# SDcard_final_rev02.net
KiCad netlist of a schematic drawn in EAGLE
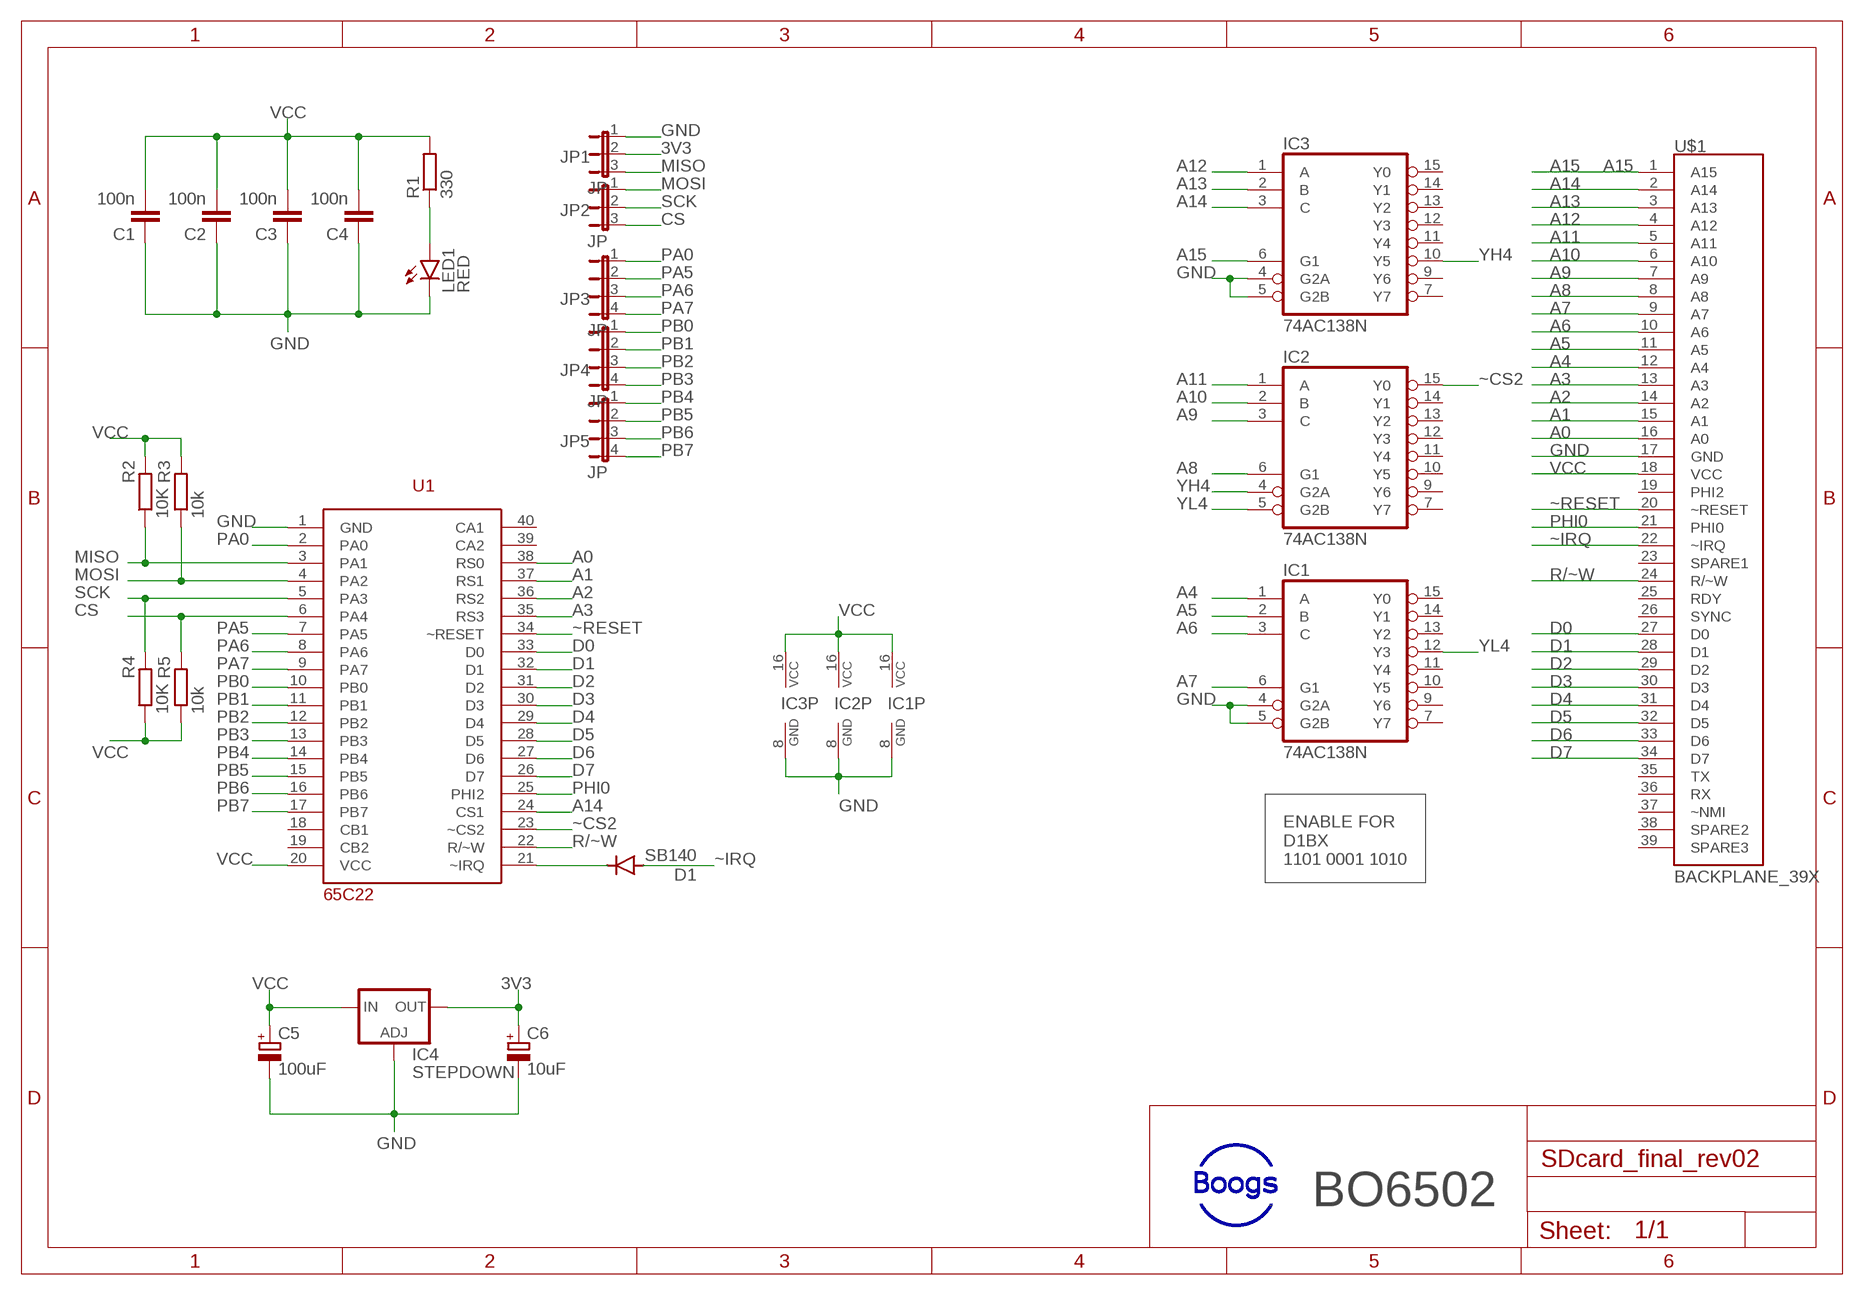
[diagram p0: schematic, sheet 1]

(export (version "E")
  (design (tool "Eeschema 10.0.6"))
  (components
    (comp (ref "C1")
      (value "100n")
      (footprint "eagle-import:C025-025X050")
      (libsource (lib "eagle-import") (part "C-EU025-025X050"))
    )
    (comp (ref "C2")
      (value "100n")
      (footprint "eagle-import:C025-025X050")
      (libsource (lib "eagle-import") (part "C-EU025-025X050"))
    )
    (comp (ref "C3")
      (value "100n")
      (footprint "eagle-import:C025-025X050")
      (libsource (lib "eagle-import") (part "C-EU025-025X050"))
    )
    (comp (ref "C4")
      (value "100n")
      (footprint "eagle-import:C025-025X050")
      (libsource (lib "eagle-import") (part "C-EU025-025X050"))
    )
    (comp (ref "C5")
      (value "100uF")
      (footprint "eagle-import:B45181A")
      (libsource (lib "eagle-import") (part "CPOL-EUB45181A"))
    )
    (comp (ref "C6")
      (value "10uF")
      (footprint "eagle-import:B45181A")
      (libsource (lib "eagle-import") (part "CPOL-EUB45181A"))
    )
    (comp (ref "D1")
      (value "SB140")
      (footprint "eagle-import:DO41-10")
      (libsource (lib "eagle-import") (part "1N4004"))
    )
    (comp (ref "IC1")
      (value "74AC138N")
      (footprint "eagle-import:DIL16")
      (libsource (lib "eagle-import") (part "74138NAC"))
    )
    (comp (ref "IC2")
      (value "74AC138N")
      (footprint "eagle-import:DIL16")
      (libsource (lib "eagle-import") (part "74138NAC"))
    )
    (comp (ref "IC3")
      (value "74AC138N")
      (footprint "eagle-import:DIL16")
      (libsource (lib "eagle-import") (part "74138NAC"))
    )
    (comp (ref "IC4")
      (value "STEPDOWN")
      (footprint "eagle-import:317TS")
      (libsource (lib "eagle-import") (part "LM317TS"))
    )
    (comp (ref "JP1")
      (value "JP")
      (footprint "eagle-import:JP2")
      (libsource (lib "eagle-import") (part "JP2E"))
    )
    (comp (ref "JP2")
      (value "JP")
      (footprint "eagle-import:JP2")
      (libsource (lib "eagle-import") (part "JP2E"))
    )
    (comp (ref "JP3")
      (value "JP")
      (footprint "eagle-import:JP4")
      (libsource (lib "eagle-import") (part "JP4E"))
    )
    (comp (ref "JP4")
      (value "JP")
      (footprint "eagle-import:JP4")
      (libsource (lib "eagle-import") (part "JP4E"))
    )
    (comp (ref "JP5")
      (value "JP")
      (footprint "eagle-import:JP4")
      (libsource (lib "eagle-import") (part "JP4E"))
    )
    (comp (ref "LED1")
      (value "RED")
      (footprint "eagle-import:LED5MM")
      (libsource (lib "eagle-import") (part "LED5MM"))
    )
    (comp (ref "R1")
      (value "330")
      (footprint "eagle-import:0207_10")
      (libsource (lib "eagle-import") (part "R-EU_0207/10"))
    )
    (comp (ref "R2")
      (value "10K")
      (footprint "eagle-import:0207_10")
      (libsource (lib "eagle-import") (part "R-EU_0207/10"))
    )
    (comp (ref "R3")
      (value "10k")
      (footprint "eagle-import:0207_10")
      (libsource (lib "eagle-import") (part "R-EU_0207/10"))
    )
    (comp (ref "R4")
      (value "10K")
      (footprint "eagle-import:0207_10")
      (libsource (lib "eagle-import") (part "R-EU_0207/10"))
    )
    (comp (ref "R5")
      (value "10k")
      (footprint "eagle-import:0207_10")
      (libsource (lib "eagle-import") (part "R-EU_0207/10"))
    )
    (comp (ref "U$1")
      (value "BACKPLANE_39X")
      (footprint "eagle-import:BP_39X")
      (fields (field (name "A15") "A15"))
      (libsource (lib "eagle-import") (part "BACKPLANE_39X"))
    )
    (comp (ref "U1")
      (value "65C22")
      (footprint "eagle-import:DIL40")
      (libsource (lib "eagle-import") (part "65C22"))
    )
  )
  (nets
    (net (code "1") (name "/3V3") (class "Default")
      (node (ref "C6") (pin "+") (pinfunction "+_+") (pintype "passive"))
      (node (ref "IC4") (pin "2") (pinfunction "OUT_2") (pintype "passive"))
      (node (ref "JP1") (pin "2") (pinfunction "2_2") (pintype "passive"))
    )
    (net (code "2") (name "/A0") (class "Default")
      (node (ref "U$1") (pin "16") (pinfunction "A0_16") (pintype "bidirectional"))
      (node (ref "U1") (pin "38") (pinfunction "RS0_38") (pintype "bidirectional"))
    )
    (net (code "3") (name "/A1") (class "Default")
      (node (ref "U$1") (pin "15") (pinfunction "A1_15") (pintype "bidirectional"))
      (node (ref "U1") (pin "37") (pinfunction "RS1_37") (pintype "bidirectional"))
    )
    (net (code "4") (name "/A2") (class "Default")
      (node (ref "U$1") (pin "14") (pinfunction "A2_14") (pintype "bidirectional"))
      (node (ref "U1") (pin "36") (pinfunction "RS2_36") (pintype "bidirectional"))
    )
    (net (code "5") (name "/A3") (class "Default")
      (node (ref "U$1") (pin "13") (pinfunction "A3_13") (pintype "bidirectional"))
      (node (ref "U1") (pin "35") (pinfunction "RS3_35") (pintype "bidirectional"))
    )
    (net (code "6") (name "/A4") (class "Default")
      (node (ref "IC1") (pin "1") (pinfunction "A_1") (pintype "input"))
      (node (ref "U$1") (pin "12") (pinfunction "A4_12") (pintype "bidirectional"))
    )
    (net (code "7") (name "/A5") (class "Default")
      (node (ref "IC1") (pin "2") (pinfunction "B_2") (pintype "input"))
      (node (ref "U$1") (pin "11") (pinfunction "A5_11") (pintype "bidirectional"))
    )
    (net (code "8") (name "/A6") (class "Default")
      (node (ref "IC1") (pin "3") (pinfunction "C_3") (pintype "input"))
      (node (ref "U$1") (pin "10") (pinfunction "A6_10") (pintype "bidirectional"))
    )
    (net (code "9") (name "/A7") (class "Default")
      (node (ref "IC1") (pin "6") (pinfunction "G1_6") (pintype "input"))
      (node (ref "U$1") (pin "9") (pinfunction "A7_9") (pintype "bidirectional"))
    )
    (net (code "10") (name "/A8") (class "Default")
      (node (ref "IC2") (pin "6") (pinfunction "G1_6") (pintype "input"))
      (node (ref "U$1") (pin "8") (pinfunction "A8_8") (pintype "bidirectional"))
    )
    (net (code "11") (name "/A9") (class "Default")
      (node (ref "IC2") (pin "3") (pinfunction "C_3") (pintype "input"))
      (node (ref "U$1") (pin "7") (pinfunction "A9_7") (pintype "bidirectional"))
    )
    (net (code "12") (name "/A10") (class "Default")
      (node (ref "IC2") (pin "2") (pinfunction "B_2") (pintype "input"))
      (node (ref "U$1") (pin "6") (pinfunction "A10_6") (pintype "bidirectional"))
    )
    (net (code "13") (name "/A11") (class "Default")
      (node (ref "IC2") (pin "1") (pinfunction "A_1") (pintype "input"))
      (node (ref "U$1") (pin "5") (pinfunction "A11_5") (pintype "bidirectional"))
    )
    (net (code "14") (name "/A12") (class "Default")
      (node (ref "IC3") (pin "1") (pinfunction "A_1") (pintype "input"))
      (node (ref "U$1") (pin "4") (pinfunction "A12_4") (pintype "bidirectional"))
    )
    (net (code "15") (name "/A13") (class "Default")
      (node (ref "IC3") (pin "2") (pinfunction "B_2") (pintype "input"))
      (node (ref "U$1") (pin "3") (pinfunction "A13_3") (pintype "bidirectional"))
    )
    (net (code "16") (name "/A14") (class "Default")
      (node (ref "IC3") (pin "3") (pinfunction "C_3") (pintype "input"))
      (node (ref "U$1") (pin "2") (pinfunction "A14_2") (pintype "bidirectional"))
      (node (ref "U1") (pin "24") (pinfunction "CS1_24") (pintype "bidirectional"))
    )
    (net (code "17") (name "/A15") (class "Default")
      (node (ref "IC3") (pin "6") (pinfunction "G1_6") (pintype "input"))
      (node (ref "U$1") (pin "1") (pinfunction "A15_1") (pintype "bidirectional"))
    )
    (net (code "18") (name "/CS") (class "Default")
      (node (ref "JP2") (pin "3") (pinfunction "3_3") (pintype "passive"))
      (node (ref "R5") (pin "2") (pinfunction "2_2") (pintype "passive"))
      (node (ref "U1") (pin "6") (pinfunction "PA4_6") (pintype "bidirectional"))
    )
    (net (code "19") (name "/D0") (class "Default")
      (node (ref "U$1") (pin "27") (pinfunction "D0_27") (pintype "bidirectional"))
      (node (ref "U1") (pin "33") (pinfunction "D0_33") (pintype "bidirectional"))
    )
    (net (code "20") (name "/D1") (class "Default")
      (node (ref "U$1") (pin "28") (pinfunction "D1_28") (pintype "bidirectional"))
      (node (ref "U1") (pin "32") (pinfunction "D1_32") (pintype "bidirectional"))
    )
    (net (code "21") (name "/D2") (class "Default")
      (node (ref "U$1") (pin "29") (pinfunction "D2_29") (pintype "bidirectional"))
      (node (ref "U1") (pin "31") (pinfunction "D2_31") (pintype "bidirectional"))
    )
    (net (code "22") (name "/D3") (class "Default")
      (node (ref "U$1") (pin "30") (pinfunction "D3_30") (pintype "bidirectional"))
      (node (ref "U1") (pin "30") (pinfunction "D3_30") (pintype "bidirectional"))
    )
    (net (code "23") (name "/D4") (class "Default")
      (node (ref "U$1") (pin "31") (pinfunction "D4_31") (pintype "bidirectional"))
      (node (ref "U1") (pin "29") (pinfunction "D4_29") (pintype "bidirectional"))
    )
    (net (code "24") (name "/D5") (class "Default")
      (node (ref "U$1") (pin "32") (pinfunction "D5_32") (pintype "bidirectional"))
      (node (ref "U1") (pin "28") (pinfunction "D5_28") (pintype "bidirectional"))
    )
    (net (code "25") (name "/D6") (class "Default")
      (node (ref "U$1") (pin "33") (pinfunction "D6_33") (pintype "bidirectional"))
      (node (ref "U1") (pin "27") (pinfunction "D6_27") (pintype "bidirectional"))
    )
    (net (code "26") (name "/D7") (class "Default")
      (node (ref "U$1") (pin "34") (pinfunction "D7_34") (pintype "bidirectional"))
      (node (ref "U1") (pin "26") (pinfunction "D7_26") (pintype "bidirectional"))
    )
    (net (code "27") (name "/GND") (class "Default")
      (node (ref "C1") (pin "1") (pinfunction "1_1") (pintype "passive"))
      (node (ref "C2") (pin "1") (pinfunction "1_1") (pintype "passive"))
      (node (ref "C3") (pin "1") (pinfunction "1_1") (pintype "passive"))
      (node (ref "C4") (pin "1") (pinfunction "1_1") (pintype "passive"))
      (node (ref "C5") (pin "-") (pinfunction "-_-") (pintype "passive"))
      (node (ref "C6") (pin "-") (pinfunction "-_-") (pintype "passive"))
      (node (ref "IC1") (pin "4") (pinfunction "G2A_4") (pintype "input"))
      (node (ref "IC1") (pin "5") (pinfunction "G2B_5") (pintype "input"))
      (node (ref "IC1") (pin "8") (pinfunction "GND_8") (pintype "power_in"))
      (node (ref "IC2") (pin "8") (pinfunction "GND_8") (pintype "power_in"))
      (node (ref "IC3") (pin "4") (pinfunction "G2A_4") (pintype "input"))
      (node (ref "IC3") (pin "5") (pinfunction "G2B_5") (pintype "input"))
      (node (ref "IC3") (pin "8") (pinfunction "GND_8") (pintype "power_in"))
      (node (ref "IC4") (pin "1") (pinfunction "ADJ_1") (pintype "input"))
      (node (ref "JP1") (pin "1") (pinfunction "1_1") (pintype "passive"))
      (node (ref "LED1") (pin "K") (pinfunction "C_K") (pintype "passive"))
      (node (ref "U$1") (pin "17") (pinfunction "GND_17") (pintype "bidirectional"))
      (node (ref "U1") (pin "1") (pinfunction "GND_1") (pintype "bidirectional"))
    )
    (net (code "28") (name "/MISO") (class "Default")
      (node (ref "JP1") (pin "3") (pinfunction "3_3") (pintype "passive"))
      (node (ref "R2") (pin "1") (pinfunction "1_1") (pintype "passive"))
      (node (ref "U1") (pin "3") (pinfunction "PA1_3") (pintype "bidirectional"))
    )
    (net (code "29") (name "/MOSI") (class "Default")
      (node (ref "JP2") (pin "1") (pinfunction "1_1") (pintype "passive"))
      (node (ref "R3") (pin "1") (pinfunction "1_1") (pintype "passive"))
      (node (ref "U1") (pin "4") (pinfunction "PA2_4") (pintype "bidirectional"))
    )
    (net (code "30") (name "/PA0") (class "Default")
      (node (ref "JP3") (pin "1") (pinfunction "1_1") (pintype "passive"))
      (node (ref "U1") (pin "2") (pinfunction "PA0_2") (pintype "bidirectional"))
    )
    (net (code "31") (name "/PA5") (class "Default")
      (node (ref "JP3") (pin "2") (pinfunction "2_2") (pintype "passive"))
      (node (ref "U1") (pin "7") (pinfunction "PA5_7") (pintype "bidirectional"))
    )
    (net (code "32") (name "/PA6") (class "Default")
      (node (ref "JP3") (pin "3") (pinfunction "3_3") (pintype "passive"))
      (node (ref "U1") (pin "8") (pinfunction "PA6_8") (pintype "bidirectional"))
    )
    (net (code "33") (name "/PA7") (class "Default")
      (node (ref "JP3") (pin "4") (pinfunction "4_4") (pintype "passive"))
      (node (ref "U1") (pin "9") (pinfunction "PA7_9") (pintype "bidirectional"))
    )
    (net (code "34") (name "/PB0") (class "Default")
      (node (ref "JP4") (pin "1") (pinfunction "1_1") (pintype "passive"))
      (node (ref "U1") (pin "10") (pinfunction "PB0_10") (pintype "bidirectional"))
    )
    (net (code "35") (name "/PB1") (class "Default")
      (node (ref "JP4") (pin "2") (pinfunction "2_2") (pintype "passive"))
      (node (ref "U1") (pin "11") (pinfunction "PB1_11") (pintype "bidirectional"))
    )
    (net (code "36") (name "/PB2") (class "Default")
      (node (ref "JP4") (pin "3") (pinfunction "3_3") (pintype "passive"))
      (node (ref "U1") (pin "12") (pinfunction "PB2_12") (pintype "bidirectional"))
    )
    (net (code "37") (name "/PB3") (class "Default")
      (node (ref "JP4") (pin "4") (pinfunction "4_4") (pintype "passive"))
      (node (ref "U1") (pin "13") (pinfunction "PB3_13") (pintype "bidirectional"))
    )
    (net (code "38") (name "/PB4") (class "Default")
      (node (ref "JP5") (pin "1") (pinfunction "1_1") (pintype "passive"))
      (node (ref "U1") (pin "14") (pinfunction "PB4_14") (pintype "bidirectional"))
    )
    (net (code "39") (name "/PB5") (class "Default")
      (node (ref "JP5") (pin "2") (pinfunction "2_2") (pintype "passive"))
      (node (ref "U1") (pin "15") (pinfunction "PB5_15") (pintype "bidirectional"))
    )
    (net (code "40") (name "/PB6") (class "Default")
      (node (ref "JP5") (pin "3") (pinfunction "3_3") (pintype "passive"))
      (node (ref "U1") (pin "16") (pinfunction "PB6_16") (pintype "bidirectional"))
    )
    (net (code "41") (name "/PB7") (class "Default")
      (node (ref "JP5") (pin "4") (pinfunction "4_4") (pintype "passive"))
      (node (ref "U1") (pin "17") (pinfunction "PB7_17") (pintype "bidirectional"))
    )
    (net (code "42") (name "/PHI0") (class "Default")
      (node (ref "U$1") (pin "21") (pinfunction "PHI0_21") (pintype "bidirectional"))
      (node (ref "U1") (pin "25") (pinfunction "PHI2_25") (pintype "bidirectional"))
    )
    (net (code "43") (name "/R{slash}~{W}") (class "Default")
      (node (ref "U$1") (pin "24") (pinfunction "R/~{W}_24") (pintype "bidirectional"))
      (node (ref "U1") (pin "22") (pinfunction "R/~{W}_22") (pintype "bidirectional"))
    )
    (net (code "44") (name "/SCK") (class "Default")
      (node (ref "JP2") (pin "2") (pinfunction "2_2") (pintype "passive"))
      (node (ref "R4") (pin "2") (pinfunction "2_2") (pintype "passive"))
      (node (ref "U1") (pin "5") (pinfunction "PA3_5") (pintype "bidirectional"))
    )
    (net (code "45") (name "/VCC") (class "Default")
      (node (ref "C1") (pin "2") (pinfunction "2_2") (pintype "passive"))
      (node (ref "C2") (pin "2") (pinfunction "2_2") (pintype "passive"))
      (node (ref "C3") (pin "2") (pinfunction "2_2") (pintype "passive"))
      (node (ref "C4") (pin "2") (pinfunction "2_2") (pintype "passive"))
      (node (ref "C5") (pin "+") (pinfunction "+_+") (pintype "passive"))
      (node (ref "IC1") (pin "16") (pinfunction "VCC_16") (pintype "power_in"))
      (node (ref "IC2") (pin "16") (pinfunction "VCC_16") (pintype "power_in"))
      (node (ref "IC3") (pin "16") (pinfunction "VCC_16") (pintype "power_in"))
      (node (ref "IC4") (pin "3") (pinfunction "IN_3") (pintype "input"))
      (node (ref "R1") (pin "2") (pinfunction "2_2") (pintype "passive"))
      (node (ref "R2") (pin "2") (pinfunction "2_2") (pintype "passive"))
      (node (ref "R3") (pin "2") (pinfunction "2_2") (pintype "passive"))
      (node (ref "R4") (pin "1") (pinfunction "1_1") (pintype "passive"))
      (node (ref "R5") (pin "1") (pinfunction "1_1") (pintype "passive"))
      (node (ref "U$1") (pin "18") (pinfunction "VCC_18") (pintype "bidirectional"))
      (node (ref "U1") (pin "20") (pinfunction "VCC_20") (pintype "bidirectional"))
    )
    (net (code "46") (name "/YH4") (class "Default")
      (node (ref "IC2") (pin "4") (pinfunction "G2A_4") (pintype "input"))
      (node (ref "IC3") (pin "10") (pinfunction "Y5_10") (pintype "output"))
    )
    (net (code "47") (name "/YL4") (class "Default")
      (node (ref "IC1") (pin "12") (pinfunction "Y3_12") (pintype "output"))
      (node (ref "IC2") (pin "5") (pinfunction "G2B_5") (pintype "input"))
    )
    (net (code "48") (name "/~{CS2}") (class "Default")
      (node (ref "IC2") (pin "15") (pinfunction "Y0_15") (pintype "output"))
      (node (ref "U1") (pin "23") (pinfunction "~{CS2}_23") (pintype "bidirectional"))
    )
    (net (code "49") (name "/~{IRQ}") (class "Default")
      (node (ref "D1") (pin "A") (pinfunction "A_A") (pintype "passive"))
      (node (ref "U$1") (pin "22") (pinfunction "~{IRQ}_22") (pintype "bidirectional"))
    )
    (net (code "50") (name "/~{RESET}") (class "Default")
      (node (ref "U$1") (pin "20") (pinfunction "~{RESET}_20") (pintype "bidirectional"))
      (node (ref "U1") (pin "34") (pinfunction "~{RESET}_34") (pintype "bidirectional"))
    )
    (net (code "51") (name "Net-(LED1-PadA)") (class "Default")
      (node (ref "LED1") (pin "A") (pinfunction "A_A") (pintype "passive"))
      (node (ref "R1") (pin "1") (pinfunction "1_1") (pintype "passive"))
    )
    (net (code "52") (name "Net-(U1-~{IRQ})") (class "Default")
      (node (ref "D1") (pin "C") (pinfunction "C_C") (pintype "passive"))
      (node (ref "U1") (pin "21") (pinfunction "~{IRQ}_21") (pintype "bidirectional"))
    )
    (net (code "53") (name "unconnected-(IC1A-Y0-Pad15)") (class "Default")
      (node (ref "IC1") (pin "15") (pinfunction "Y0_15") (pintype "output"))
    )
    (net (code "54") (name "unconnected-(IC1A-Y1-Pad14)") (class "Default")
      (node (ref "IC1") (pin "14") (pinfunction "Y1_14") (pintype "output"))
    )
    (net (code "55") (name "unconnected-(IC1A-Y2-Pad13)") (class "Default")
      (node (ref "IC1") (pin "13") (pinfunction "Y2_13") (pintype "output"))
    )
    (net (code "56") (name "unconnected-(IC1A-Y4-Pad11)") (class "Default")
      (node (ref "IC1") (pin "11") (pinfunction "Y4_11") (pintype "output"))
    )
    (net (code "57") (name "unconnected-(IC1A-Y5-Pad10)") (class "Default")
      (node (ref "IC1") (pin "10") (pinfunction "Y5_10") (pintype "output"))
    )
    (net (code "58") (name "unconnected-(IC1A-Y6-Pad9)") (class "Default")
      (node (ref "IC1") (pin "9") (pinfunction "Y6_9") (pintype "output"))
    )
    (net (code "59") (name "unconnected-(IC1A-Y7-Pad7)") (class "Default")
      (node (ref "IC1") (pin "7") (pinfunction "Y7_7") (pintype "output"))
    )
    (net (code "60") (name "unconnected-(IC2A-Y1-Pad14)") (class "Default")
      (node (ref "IC2") (pin "14") (pinfunction "Y1_14") (pintype "output"))
    )
    (net (code "61") (name "unconnected-(IC2A-Y2-Pad13)") (class "Default")
      (node (ref "IC2") (pin "13") (pinfunction "Y2_13") (pintype "output"))
    )
    (net (code "62") (name "unconnected-(IC2A-Y3-Pad12)") (class "Default")
      (node (ref "IC2") (pin "12") (pinfunction "Y3_12") (pintype "output"))
    )
    (net (code "63") (name "unconnected-(IC2A-Y4-Pad11)") (class "Default")
      (node (ref "IC2") (pin "11") (pinfunction "Y4_11") (pintype "output"))
    )
    (net (code "64") (name "unconnected-(IC2A-Y5-Pad10)") (class "Default")
      (node (ref "IC2") (pin "10") (pinfunction "Y5_10") (pintype "output"))
    )
    (net (code "65") (name "unconnected-(IC2A-Y6-Pad9)") (class "Default")
      (node (ref "IC2") (pin "9") (pinfunction "Y6_9") (pintype "output"))
    )
    (net (code "66") (name "unconnected-(IC2A-Y7-Pad7)") (class "Default")
      (node (ref "IC2") (pin "7") (pinfunction "Y7_7") (pintype "output"))
    )
    (net (code "67") (name "unconnected-(IC3A-Y0-Pad15)") (class "Default")
      (node (ref "IC3") (pin "15") (pinfunction "Y0_15") (pintype "output"))
    )
    (net (code "68") (name "unconnected-(IC3A-Y1-Pad14)") (class "Default")
      (node (ref "IC3") (pin "14") (pinfunction "Y1_14") (pintype "output"))
    )
    (net (code "69") (name "unconnected-(IC3A-Y2-Pad13)") (class "Default")
      (node (ref "IC3") (pin "13") (pinfunction "Y2_13") (pintype "output"))
    )
    (net (code "70") (name "unconnected-(IC3A-Y3-Pad12)") (class "Default")
      (node (ref "IC3") (pin "12") (pinfunction "Y3_12") (pintype "output"))
    )
    (net (code "71") (name "unconnected-(IC3A-Y4-Pad11)") (class "Default")
      (node (ref "IC3") (pin "11") (pinfunction "Y4_11") (pintype "output"))
    )
    (net (code "72") (name "unconnected-(IC3A-Y6-Pad9)") (class "Default")
      (node (ref "IC3") (pin "9") (pinfunction "Y6_9") (pintype "output"))
    )
    (net (code "73") (name "unconnected-(IC3A-Y7-Pad7)") (class "Default")
      (node (ref "IC3") (pin "7") (pinfunction "Y7_7") (pintype "output"))
    )
    (net (code "74") (name "unconnected-(U$1-PHI2-Pad19)") (class "Default")
      (node (ref "U$1") (pin "19") (pinfunction "PHI2_19") (pintype "bidirectional"))
    )
    (net (code "75") (name "unconnected-(U$1-RDY-Pad25)") (class "Default")
      (node (ref "U$1") (pin "25") (pinfunction "RDY_25") (pintype "bidirectional"))
    )
    (net (code "76") (name "unconnected-(U$1-RX-Pad36)") (class "Default")
      (node (ref "U$1") (pin "36") (pinfunction "RX_36") (pintype "bidirectional"))
    )
    (net (code "77") (name "unconnected-(U$1-SPARE1-Pad23)") (class "Default")
      (node (ref "U$1") (pin "23") (pinfunction "SPARE1_23") (pintype "bidirectional"))
    )
    (net (code "78") (name "unconnected-(U$1-SPARE2-Pad38)") (class "Default")
      (node (ref "U$1") (pin "38") (pinfunction "SPARE2_38") (pintype "bidirectional"))
    )
    (net (code "79") (name "unconnected-(U$1-SPARE3-Pad39)") (class "Default")
      (node (ref "U$1") (pin "39") (pinfunction "SPARE3_39") (pintype "bidirectional"))
    )
    (net (code "80") (name "unconnected-(U$1-SYNC-Pad26)") (class "Default")
      (node (ref "U$1") (pin "26") (pinfunction "SYNC_26") (pintype "bidirectional"))
    )
    (net (code "81") (name "unconnected-(U$1-TX-Pad35)") (class "Default")
      (node (ref "U$1") (pin "35") (pinfunction "TX_35") (pintype "bidirectional"))
    )
    (net (code "82") (name "unconnected-(U$1-~{NMI}-Pad37)") (class "Default")
      (node (ref "U$1") (pin "37") (pinfunction "~{NMI}_37") (pintype "bidirectional"))
    )
    (net (code "83") (name "unconnected-(U1-CA1-Pad40)") (class "Default")
      (node (ref "U1") (pin "40") (pinfunction "CA1_40") (pintype "bidirectional"))
    )
    (net (code "84") (name "unconnected-(U1-CA2-Pad39)") (class "Default")
      (node (ref "U1") (pin "39") (pinfunction "CA2_39") (pintype "bidirectional"))
    )
    (net (code "85") (name "unconnected-(U1-CB1-Pad18)") (class "Default")
      (node (ref "U1") (pin "18") (pinfunction "CB1_18") (pintype "bidirectional"))
    )
    (net (code "86") (name "unconnected-(U1-CB2-Pad19)") (class "Default")
      (node (ref "U1") (pin "19") (pinfunction "CB2_19") (pintype "bidirectional"))
    )
  )
)
